# Interfase_1_Main.net
KiCad netlist of a schematic drawn in EAGLE
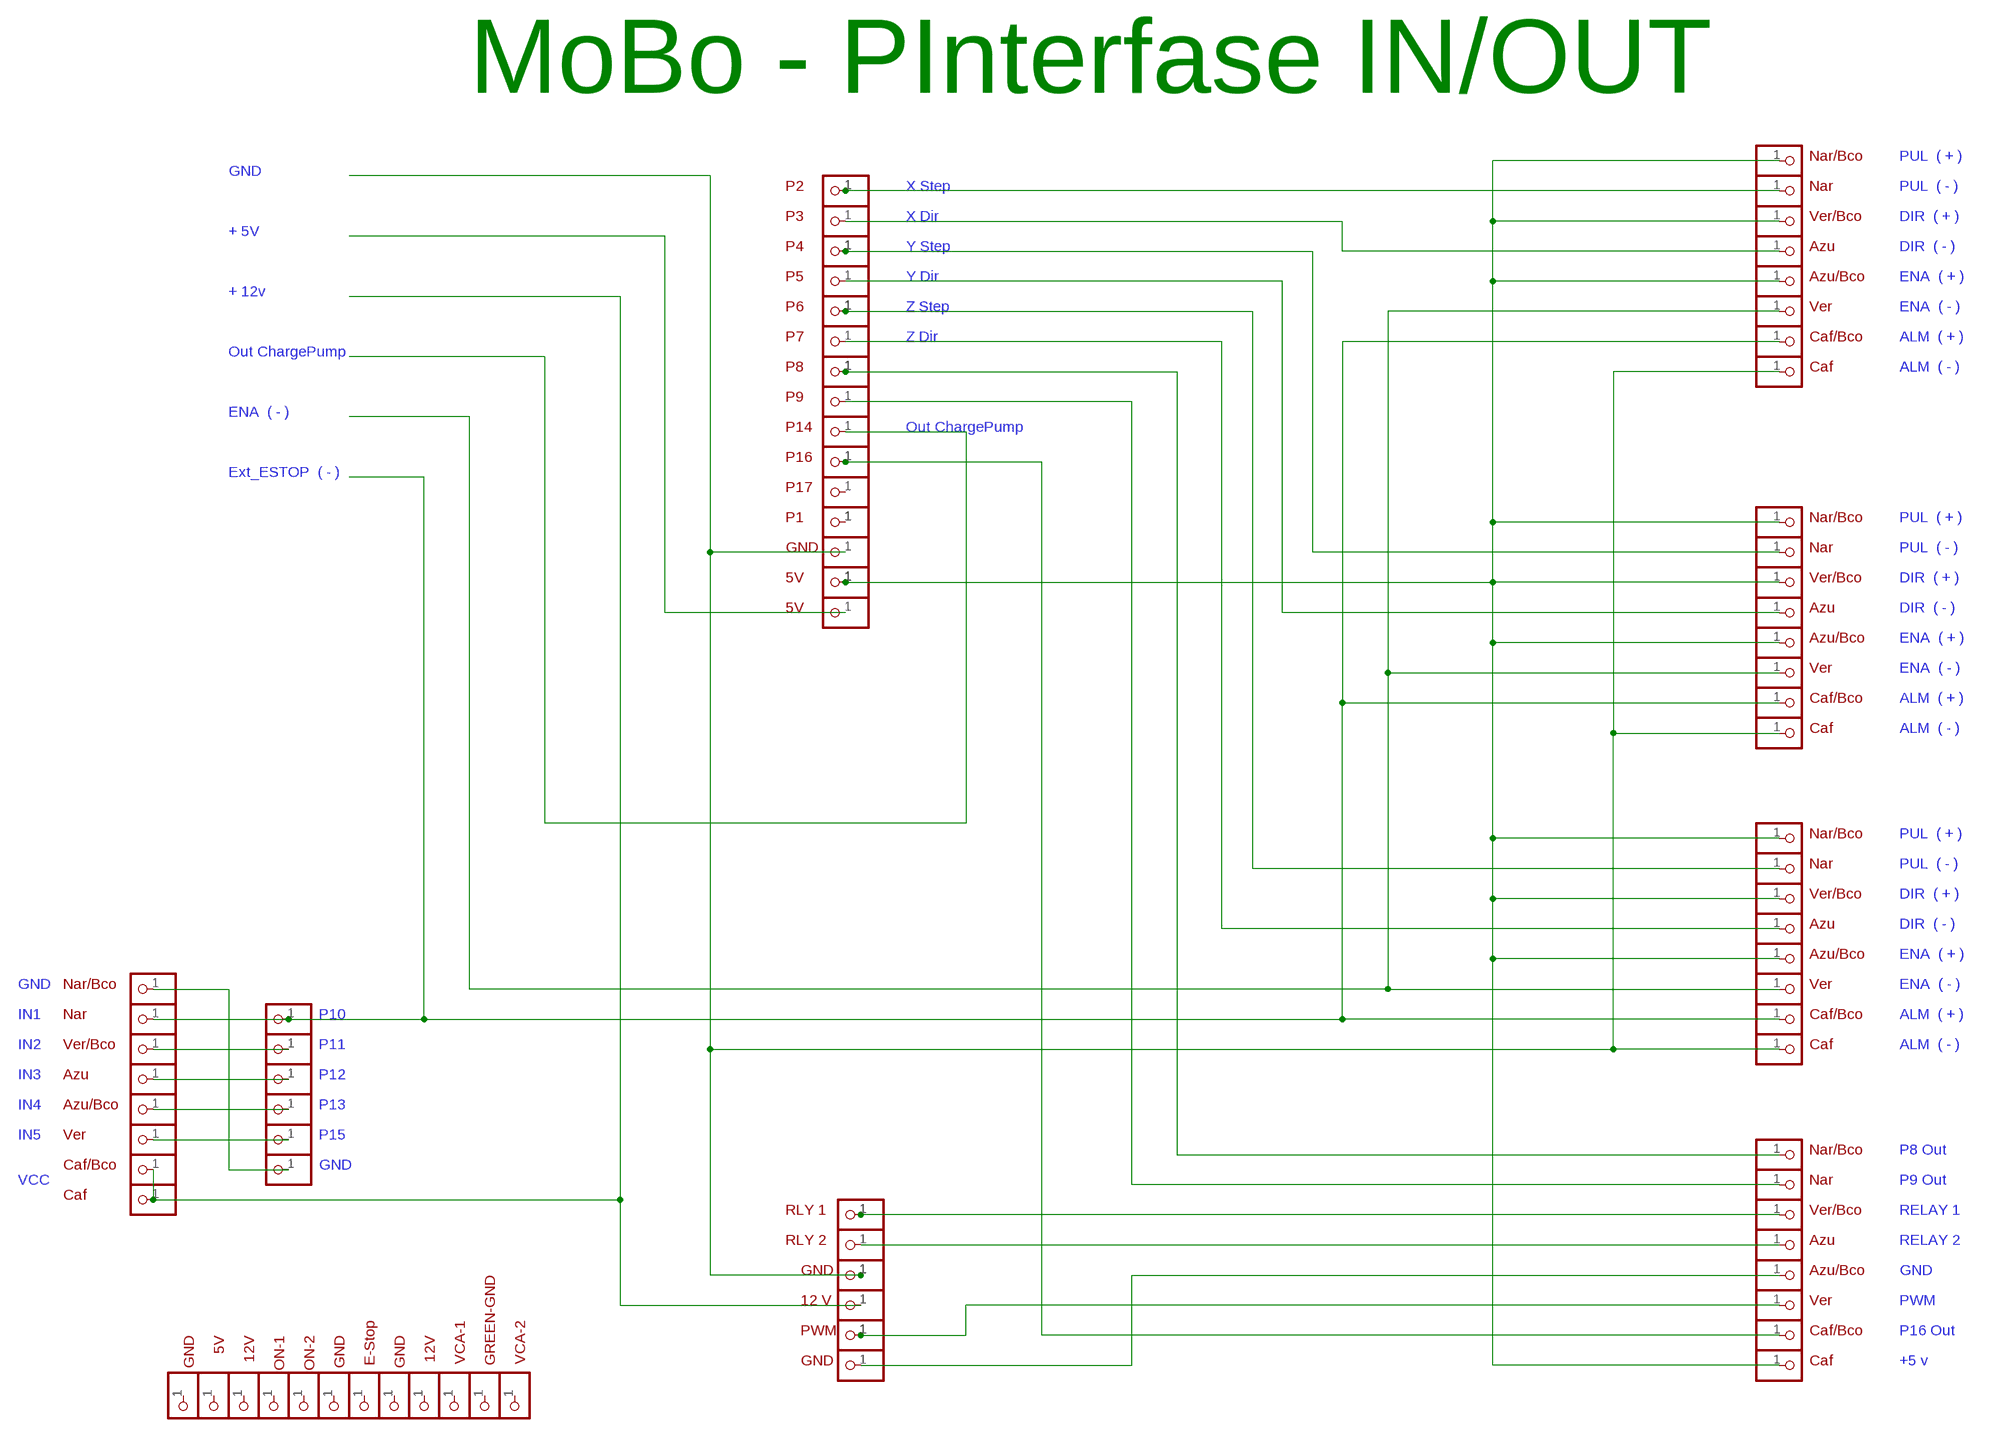
[diagram p0: schematic, sheet 1]

(export (version "E")
  (design (tool "Eeschema 10.0.6"))
  (components
    (comp (ref "JP1")
      (value "ioiooo")
      (footprint "eagle-import:1X01")
      (fields (field (name "MANUFACTURER") "Generic"))
      (libsource (lib "eagle-import") (part "PINHD-1X1"))
    )
    (comp (ref "JP2")
      (value "ioiooo")
      (footprint "eagle-import:1X01")
      (fields (field (name "MANUFACTURER") "Generic"))
      (libsource (lib "eagle-import") (part "PINHD-1X1"))
    )
    (comp (ref "JP3")
      (value "ioiooo")
      (footprint "eagle-import:1X01")
      (fields (field (name "MANUFACTURER") "Generic"))
      (libsource (lib "eagle-import") (part "PINHD-1X1"))
    )
    (comp (ref "JP4")
      (value "ioiooo")
      (footprint "eagle-import:1X01")
      (fields (field (name "MANUFACTURER") "Generic"))
      (libsource (lib "eagle-import") (part "PINHD-1X1"))
    )
    (comp (ref "JP5")
      (value "ioiooo")
      (footprint "eagle-import:1X01")
      (fields (field (name "MANUFACTURER") "Generic"))
      (libsource (lib "eagle-import") (part "PINHD-1X1"))
    )
    (comp (ref "JP6")
      (value "ioiooo")
      (footprint "eagle-import:1X01")
      (fields (field (name "MANUFACTURER") "Generic"))
      (libsource (lib "eagle-import") (part "PINHD-1X1"))
    )
    (comp (ref "JP7")
      (value "ioiooo")
      (footprint "eagle-import:1X01")
      (fields (field (name "MANUFACTURER") "Generic"))
      (libsource (lib "eagle-import") (part "PINHD-1X1"))
    )
    (comp (ref "JP8")
      (value "ioiooo")
      (footprint "eagle-import:1X01")
      (fields (field (name "MANUFACTURER") "Generic"))
      (libsource (lib "eagle-import") (part "PINHD-1X1"))
    )
    (comp (ref "JP9")
      (value "ioiooo")
      (footprint "eagle-import:1X01")
      (fields (field (name "MANUFACTURER") "Generic"))
      (libsource (lib "eagle-import") (part "PINHD-1X1"))
    )
    (comp (ref "JP10")
      (value "ioiooo")
      (footprint "eagle-import:1X01")
      (fields (field (name "MANUFACTURER") "Generic"))
      (libsource (lib "eagle-import") (part "PINHD-1X1"))
    )
    (comp (ref "JP11")
      (value "ioiooo")
      (footprint "eagle-import:1X01")
      (fields (field (name "MANUFACTURER") "Generic"))
      (libsource (lib "eagle-import") (part "PINHD-1X1"))
    )
    (comp (ref "JP12")
      (value "ioiooo")
      (footprint "eagle-import:1X01")
      (fields (field (name "MANUFACTURER") "Generic"))
      (libsource (lib "eagle-import") (part "PINHD-1X1"))
    )
    (comp (ref "JP13")
      (value "ioiooo")
      (footprint "eagle-import:1X01")
      (fields (field (name "MANUFACTURER") "Generic"))
      (libsource (lib "eagle-import") (part "PINHD-1X1"))
    )
    (comp (ref "JP14")
      (value "ioiooo")
      (footprint "eagle-import:1X01")
      (fields (field (name "MANUFACTURER") "Generic"))
      (libsource (lib "eagle-import") (part "PINHD-1X1"))
    )
    (comp (ref "JP15")
      (value "ioiooo")
      (footprint "eagle-import:1X01")
      (fields (field (name "MANUFACTURER") "Generic"))
      (libsource (lib "eagle-import") (part "PINHD-1X1"))
    )
    (comp (ref "JP16")
      (value "ioiooo")
      (footprint "eagle-import:1X01")
      (fields (field (name "MANUFACTURER") "Generic"))
      (libsource (lib "eagle-import") (part "PINHD-1X1"))
    )
    (comp (ref "JP17")
      (value "ioiooo")
      (footprint "eagle-import:1X01")
      (fields (field (name "MANUFACTURER") "Generic"))
      (libsource (lib "eagle-import") (part "PINHD-1X1"))
    )
    (comp (ref "JP18")
      (value "ioiooo")
      (footprint "eagle-import:1X01")
      (fields (field (name "MANUFACTURER") "Generic"))
      (libsource (lib "eagle-import") (part "PINHD-1X1"))
    )
    (comp (ref "JP19")
      (value "ioiooo")
      (footprint "eagle-import:1X01")
      (fields (field (name "MANUFACTURER") "Generic"))
      (libsource (lib "eagle-import") (part "PINHD-1X1"))
    )
    (comp (ref "JP20")
      (value "ioiooo")
      (footprint "eagle-import:1X01")
      (fields (field (name "MANUFACTURER") "Generic"))
      (libsource (lib "eagle-import") (part "PINHD-1X1"))
    )
    (comp (ref "JP21")
      (value "ioiooo")
      (footprint "eagle-import:1X01")
      (fields (field (name "MANUFACTURER") "Generic"))
      (libsource (lib "eagle-import") (part "PINHD-1X1"))
    )
    (comp (ref "JP22")
      (value "ioiooo")
      (footprint "eagle-import:1X01")
      (fields (field (name "MANUFACTURER") "Generic"))
      (libsource (lib "eagle-import") (part "PINHD-1X1"))
    )
    (comp (ref "JP23")
      (value "ioiooo")
      (footprint "eagle-import:1X01")
      (fields (field (name "MANUFACTURER") "Generic"))
      (libsource (lib "eagle-import") (part "PINHD-1X1"))
    )
    (comp (ref "JP24")
      (value "ioiooo")
      (footprint "eagle-import:1X01")
      (fields (field (name "MANUFACTURER") "Generic"))
      (libsource (lib "eagle-import") (part "PINHD-1X1"))
    )
    (comp (ref "JP25")
      (value "ioiooo")
      (footprint "eagle-import:1X01")
      (fields (field (name "MANUFACTURER") "Generic"))
      (libsource (lib "eagle-import") (part "PINHD-1X1"))
    )
    (comp (ref "JP26")
      (value "ioiooo")
      (footprint "eagle-import:1X01")
      (fields (field (name "MANUFACTURER") "Generic"))
      (libsource (lib "eagle-import") (part "PINHD-1X1"))
    )
    (comp (ref "JP27")
      (value "ioiooo")
      (footprint "eagle-import:1X01")
      (fields (field (name "MANUFACTURER") "Generic"))
      (libsource (lib "eagle-import") (part "PINHD-1X1"))
    )
    (comp (ref "JP28")
      (value "ioiooo")
      (footprint "eagle-import:1X01")
      (fields (field (name "MANUFACTURER") "Generic"))
      (libsource (lib "eagle-import") (part "PINHD-1X1"))
    )
    (comp (ref "JP29")
      (value "ioiooo")
      (footprint "eagle-import:1X01")
      (fields (field (name "MANUFACTURER") "Generic"))
      (libsource (lib "eagle-import") (part "PINHD-1X1"))
    )
    (comp (ref "JP30")
      (value "ioiooo")
      (footprint "eagle-import:1X01")
      (fields (field (name "MANUFACTURER") "Generic"))
      (libsource (lib "eagle-import") (part "PINHD-1X1"))
    )
    (comp (ref "JP31")
      (value "ioiooo")
      (footprint "eagle-import:1X01")
      (fields (field (name "MANUFACTURER") "Generic"))
      (libsource (lib "eagle-import") (part "PINHD-1X1"))
    )
    (comp (ref "JP32")
      (value "ioiooo")
      (footprint "eagle-import:1X01")
      (fields (field (name "MANUFACTURER") "Generic"))
      (libsource (lib "eagle-import") (part "PINHD-1X1"))
    )
    (comp (ref "JP33")
      (value "ioiooo")
      (footprint "eagle-import:1X01")
      (fields (field (name "MANUFACTURER") "Generic"))
      (libsource (lib "eagle-import") (part "PINHD-1X1"))
    )
    (comp (ref "JP34")
      (value "ioiooo")
      (footprint "eagle-import:1X01")
      (fields (field (name "MANUFACTURER") "Generic"))
      (libsource (lib "eagle-import") (part "PINHD-1X1"))
    )
    (comp (ref "JP35")
      (value "ioiooo")
      (footprint "eagle-import:1X01")
      (fields (field (name "MANUFACTURER") "Generic"))
      (libsource (lib "eagle-import") (part "PINHD-1X1"))
    )
    (comp (ref "JP36")
      (value "ioiooo")
      (footprint "eagle-import:1X01")
      (fields (field (name "MANUFACTURER") "Generic"))
      (libsource (lib "eagle-import") (part "PINHD-1X1"))
    )
    (comp (ref "JP37")
      (value "ioiooo")
      (footprint "eagle-import:1X01")
      (fields (field (name "MANUFACTURER") "Generic"))
      (libsource (lib "eagle-import") (part "PINHD-1X1"))
    )
    (comp (ref "JP38")
      (value "ioiooo")
      (footprint "eagle-import:1X01")
      (fields (field (name "MANUFACTURER") "Generic"))
      (libsource (lib "eagle-import") (part "PINHD-1X1"))
    )
    (comp (ref "JP39")
      (value "ioiooo")
      (footprint "eagle-import:1X01")
      (fields (field (name "MANUFACTURER") "Generic"))
      (libsource (lib "eagle-import") (part "PINHD-1X1"))
    )
    (comp (ref "JP40")
      (value "ioiooo")
      (footprint "eagle-import:1X01")
      (fields (field (name "MANUFACTURER") "Generic"))
      (libsource (lib "eagle-import") (part "PINHD-1X1"))
    )
    (comp (ref "JP41")
      (value "ioiooo")
      (footprint "eagle-import:1X01")
      (fields (field (name "MANUFACTURER") "Generic"))
      (libsource (lib "eagle-import") (part "PINHD-1X1"))
    )
    (comp (ref "JP42")
      (value "ioiooo")
      (footprint "eagle-import:1X01")
      (fields (field (name "MANUFACTURER") "Generic"))
      (libsource (lib "eagle-import") (part "PINHD-1X1"))
    )
    (comp (ref "JP43")
      (value "ioiooo")
      (footprint "eagle-import:1X01")
      (fields (field (name "MANUFACTURER") "Generic"))
      (libsource (lib "eagle-import") (part "PINHD-1X1"))
    )
    (comp (ref "JP44")
      (value "ioiooo")
      (footprint "eagle-import:1X01")
      (fields (field (name "MANUFACTURER") "Generic"))
      (libsource (lib "eagle-import") (part "PINHD-1X1"))
    )
    (comp (ref "JP45")
      (value "ioiooo")
      (footprint "eagle-import:1X01")
      (fields (field (name "MANUFACTURER") "Generic"))
      (libsource (lib "eagle-import") (part "PINHD-1X1"))
    )
    (comp (ref "JP46")
      (value "ioiooo")
      (footprint "eagle-import:1X01")
      (fields (field (name "MANUFACTURER") "Generic"))
      (libsource (lib "eagle-import") (part "PINHD-1X1"))
    )
    (comp (ref "JP47")
      (value "ioiooo")
      (footprint "eagle-import:1X01")
      (fields (field (name "MANUFACTURER") "Generic"))
      (libsource (lib "eagle-import") (part "PINHD-1X1"))
    )
    (comp (ref "JP48")
      (value "ioiooo")
      (footprint "eagle-import:1X01")
      (fields (field (name "MANUFACTURER") "Generic"))
      (libsource (lib "eagle-import") (part "PINHD-1X1"))
    )
    (comp (ref "JP49")
      (value "ioiooo")
      (footprint "eagle-import:1X01")
      (fields (field (name "MANUFACTURER") "Generic"))
      (libsource (lib "eagle-import") (part "PINHD-1X1"))
    )
    (comp (ref "JP50")
      (value "ioiooo")
      (footprint "eagle-import:1X01")
      (fields (field (name "MANUFACTURER") "Generic"))
      (libsource (lib "eagle-import") (part "PINHD-1X1"))
    )
    (comp (ref "JP51")
      (value "ioiooo")
      (footprint "eagle-import:1X01")
      (fields (field (name "MANUFACTURER") "Generic"))
      (libsource (lib "eagle-import") (part "PINHD-1X1"))
    )
    (comp (ref "JP52")
      (value "ioiooo")
      (footprint "eagle-import:1X01")
      (fields (field (name "MANUFACTURER") "Generic"))
      (libsource (lib "eagle-import") (part "PINHD-1X1"))
    )
    (comp (ref "JP53")
      (value "ioiooo")
      (footprint "eagle-import:1X01")
      (fields (field (name "MANUFACTURER") "Generic"))
      (libsource (lib "eagle-import") (part "PINHD-1X1"))
    )
    (comp (ref "JP54")
      (value "ioiooo")
      (footprint "eagle-import:1X01")
      (fields (field (name "MANUFACTURER") "Generic"))
      (libsource (lib "eagle-import") (part "PINHD-1X1"))
    )
    (comp (ref "JP55")
      (value "ioiooo")
      (footprint "eagle-import:1X01")
      (fields (field (name "MANUFACTURER") "Generic"))
      (libsource (lib "eagle-import") (part "PINHD-1X1"))
    )
    (comp (ref "JP56")
      (value "ioiooo")
      (footprint "eagle-import:1X01")
      (fields (field (name "MANUFACTURER") "Generic"))
      (libsource (lib "eagle-import") (part "PINHD-1X1"))
    )
    (comp (ref "JP57")
      (value "ioiooo")
      (footprint "eagle-import:1X01")
      (fields (field (name "MANUFACTURER") "Generic"))
      (libsource (lib "eagle-import") (part "PINHD-1X1"))
    )
    (comp (ref "JP58")
      (value "ioiooo")
      (footprint "eagle-import:1X01")
      (fields (field (name "MANUFACTURER") "Generic"))
      (libsource (lib "eagle-import") (part "PINHD-1X1"))
    )
    (comp (ref "JP59")
      (value "ioiooo")
      (footprint "eagle-import:1X01")
      (fields (field (name "MANUFACTURER") "Generic"))
      (libsource (lib "eagle-import") (part "PINHD-1X1"))
    )
    (comp (ref "JP60")
      (value "ioiooo")
      (footprint "eagle-import:1X01")
      (fields (field (name "MANUFACTURER") "Generic"))
      (libsource (lib "eagle-import") (part "PINHD-1X1"))
    )
    (comp (ref "JP61")
      (value "ioiooo")
      (footprint "eagle-import:1X01")
      (fields (field (name "MANUFACTURER") "Generic"))
      (libsource (lib "eagle-import") (part "PINHD-1X1"))
    )
    (comp (ref "JP62")
      (value "ioiooo")
      (footprint "eagle-import:1X01")
      (fields (field (name "MANUFACTURER") "Generic"))
      (libsource (lib "eagle-import") (part "PINHD-1X1"))
    )
    (comp (ref "JP63")
      (value "ioiooo")
      (footprint "eagle-import:1X01")
      (fields (field (name "MANUFACTURER") "Generic"))
      (libsource (lib "eagle-import") (part "PINHD-1X1"))
    )
    (comp (ref "JP64")
      (value "ioiooo")
      (footprint "eagle-import:1X01")
      (fields (field (name "MANUFACTURER") "Generic"))
      (libsource (lib "eagle-import") (part "PINHD-1X1"))
    )
    (comp (ref "JP65")
      (value "ioiooo")
      (footprint "eagle-import:1X01")
      (fields (field (name "MANUFACTURER") "Generic"))
      (libsource (lib "eagle-import") (part "PINHD-1X1"))
    )
    (comp (ref "JP66")
      (value "ioiooo")
      (footprint "eagle-import:1X01")
      (fields (field (name "MANUFACTURER") "Generic"))
      (libsource (lib "eagle-import") (part "PINHD-1X1"))
    )
    (comp (ref "JP67")
      (value "ioiooo")
      (footprint "eagle-import:1X01")
      (fields (field (name "MANUFACTURER") "Generic"))
      (libsource (lib "eagle-import") (part "PINHD-1X1"))
    )
    (comp (ref "JP68")
      (value "ioiooo")
      (footprint "eagle-import:1X01")
      (fields (field (name "MANUFACTURER") "Generic"))
      (libsource (lib "eagle-import") (part "PINHD-1X1"))
    )
    (comp (ref "JP69")
      (value "ioiooo")
      (footprint "eagle-import:1X01")
      (fields (field (name "MANUFACTURER") "Generic"))
      (libsource (lib "eagle-import") (part "PINHD-1X1"))
    )
    (comp (ref "JP70")
      (value "ioiooo")
      (footprint "eagle-import:1X01")
      (fields (field (name "MANUFACTURER") "Generic"))
      (libsource (lib "eagle-import") (part "PINHD-1X1"))
    )
    (comp (ref "JP71")
      (value "ioiooo")
      (footprint "eagle-import:1X01")
      (fields (field (name "MANUFACTURER") "Generic"))
      (libsource (lib "eagle-import") (part "PINHD-1X1"))
    )
    (comp (ref "JP72")
      (value "ioiooo")
      (footprint "eagle-import:1X01")
      (fields (field (name "MANUFACTURER") "Generic"))
      (libsource (lib "eagle-import") (part "PINHD-1X1"))
    )
    (comp (ref "JP73")
      (value "ioiooo")
      (footprint "eagle-import:1X01")
      (fields (field (name "MANUFACTURER") "Generic"))
      (libsource (lib "eagle-import") (part "PINHD-1X1"))
    )
    (comp (ref "JP74")
      (value "ioiooo")
      (footprint "eagle-import:1X01")
      (fields (field (name "MANUFACTURER") "Generic"))
      (libsource (lib "eagle-import") (part "PINHD-1X1"))
    )
    (comp (ref "JP75")
      (value "ioiooo")
      (footprint "eagle-import:1X01")
      (fields (field (name "MANUFACTURER") "Generic"))
      (libsource (lib "eagle-import") (part "PINHD-1X1"))
    )
    (comp (ref "JP76")
      (value "ioiooo")
      (footprint "eagle-import:1X01")
      (fields (field (name "MANUFACTURER") "Generic"))
      (libsource (lib "eagle-import") (part "PINHD-1X1"))
    )
    (comp (ref "JP77")
      (value "ioiooo")
      (footprint "eagle-import:1X01")
      (fields (field (name "MANUFACTURER") "Generic"))
      (libsource (lib "eagle-import") (part "PINHD-1X1"))
    )
    (comp (ref "JP78")
      (value "ioiooo")
      (footprint "eagle-import:1X01")
      (fields (field (name "MANUFACTURER") "Generic"))
      (libsource (lib "eagle-import") (part "PINHD-1X1"))
    )
    (comp (ref "JP79")
      (value "ioiooo")
      (footprint "eagle-import:1X01")
      (fields (field (name "MANUFACTURER") "Generic"))
      (libsource (lib "eagle-import") (part "PINHD-1X1"))
    )
    (comp (ref "JP80")
      (value "ioiooo")
      (footprint "eagle-import:1X01")
      (fields (field (name "MANUFACTURER") "Generic"))
      (libsource (lib "eagle-import") (part "PINHD-1X1"))
    )
    (comp (ref "JP81")
      (value "ioiooo")
      (footprint "eagle-import:1X01")
      (fields (field (name "MANUFACTURER") "Generic"))
      (libsource (lib "eagle-import") (part "PINHD-1X1"))
    )
    (comp (ref "JP82")
      (value "ioiooo")
      (footprint "eagle-import:1X01")
      (fields (field (name "MANUFACTURER") "Generic"))
      (libsource (lib "eagle-import") (part "PINHD-1X1"))
    )
    (comp (ref "JP83")
      (value "ioiooo")
      (footprint "eagle-import:1X01")
      (fields (field (name "MANUFACTURER") "Generic"))
      (libsource (lib "eagle-import") (part "PINHD-1X1"))
    )
    (comp (ref "JP84")
      (value "ioiooo")
      (footprint "eagle-import:1X01")
      (fields (field (name "MANUFACTURER") "Generic"))
      (libsource (lib "eagle-import") (part "PINHD-1X1"))
    )
    (comp (ref "JP85")
      (value "ioiooo")
      (footprint "eagle-import:1X01")
      (fields (field (name "MANUFACTURER") "Generic"))
      (libsource (lib "eagle-import") (part "PINHD-1X1"))
    )
    (comp (ref "JP86")
      (value "ioiooo")
      (footprint "eagle-import:1X01")
      (fields (field (name "MANUFACTURER") "Generic"))
      (libsource (lib "eagle-import") (part "PINHD-1X1"))
    )
    (comp (ref "JP87")
      (value "ioiooo")
      (footprint "eagle-import:1X01")
      (fields (field (name "MANUFACTURER") "Generic"))
      (libsource (lib "eagle-import") (part "PINHD-1X1"))
    )
    (comp (ref "JP88")
      (value "ioiooo")
      (footprint "eagle-import:1X01")
      (fields (field (name "MANUFACTURER") "Generic"))
      (libsource (lib "eagle-import") (part "PINHD-1X1"))
    )
    (comp (ref "JP89")
      (value "ioiooo")
      (footprint "eagle-import:1X01")
      (fields (field (name "MANUFACTURER") "Generic"))
      (libsource (lib "eagle-import") (part "PINHD-1X1"))
    )
  )
  (nets
    (net (code "1") (name "Net-(JP1-Pad1)") (class "Default")
      (node (ref "JP1") (pin "1") (pinfunction "1_1") (pintype "passive"))
      (node (ref "JP15") (pin "1") (pinfunction "1_1") (pintype "passive"))
      (node (ref "JP17") (pin "1") (pinfunction "1_1") (pintype "passive"))
      (node (ref "JP29") (pin "1") (pinfunction "1_1") (pintype "passive"))
      (node (ref "JP31") (pin "1") (pinfunction "1_1") (pintype "passive"))
      (node (ref "JP32") (pin "1") (pinfunction "1_1") (pintype "passive"))
      (node (ref "JP35") (pin "1") (pinfunction "1_1") (pintype "passive"))
      (node (ref "JP37") (pin "1") (pinfunction "1_1") (pintype "passive"))
      (node (ref "JP41") (pin "1") (pinfunction "1_1") (pintype "passive"))
      (node (ref "JP43") (pin "1") (pinfunction "1_1") (pintype "passive"))
      (node (ref "JP45") (pin "1") (pinfunction "1_1") (pintype "passive"))
      (node (ref "JP54") (pin "1") (pinfunction "1_1") (pintype "passive"))
    )
    (net (code "2") (name "Net-(JP2-Pad1)") (class "Default")
      (node (ref "JP2") (pin "1") (pinfunction "1_1") (pintype "passive"))
      (node (ref "JP3") (pin "1") (pinfunction "1_1") (pintype "passive"))
      (node (ref "JP4") (pin "1") (pinfunction "1_1") (pintype "passive"))
    )
    (net (code "3") (name "Net-(JP10-Pad1)") (class "Default")
      (node (ref "JP10") (pin "1") (pinfunction "1_1") (pintype "passive"))
      (node (ref "JP42") (pin "1") (pinfunction "1_1") (pintype "passive"))
      (node (ref "JP9") (pin "1") (pinfunction "1_1") (pintype "passive"))
    )
    (net (code "4") (name "Net-(JP11-Pad1)") (class "Default")
      (node (ref "JP11") (pin "1") (pinfunction "1_1") (pintype "passive"))
      (node (ref "JP44") (pin "1") (pinfunction "1_1") (pintype "passive"))
    )
    (net (code "5") (name "Net-(JP12-Pad1)") (class "Default")
      (node (ref "JP12") (pin "1") (pinfunction "1_1") (pintype "passive"))
      (node (ref "JP13") (pin "1") (pinfunction "1_1") (pintype "passive"))
      (node (ref "JP27") (pin "1") (pinfunction "1_1") (pintype "passive"))
    )
    (net (code "6") (name "Net-(JP14-Pad1)") (class "Default")
      (node (ref "JP14") (pin "1") (pinfunction "1_1") (pintype "passive"))
      (node (ref "JP28") (pin "1") (pinfunction "1_1") (pintype "passive"))
    )
    (net (code "7") (name "Net-(JP16-Pad1)") (class "Default")
      (node (ref "JP16") (pin "1") (pinfunction "1_1") (pintype "passive"))
      (node (ref "JP5") (pin "1") (pinfunction "1_1") (pintype "passive"))
    )
    (net (code "8") (name "Net-(JP18-Pad1)") (class "Default")
      (node (ref "JP18") (pin "1") (pinfunction "1_1") (pintype "passive"))
      (node (ref "JP38") (pin "1") (pinfunction "1_1") (pintype "passive"))
      (node (ref "JP46") (pin "1") (pinfunction "1_1") (pintype "passive"))
    )
    (net (code "9") (name "Net-(JP19-Pad1)") (class "Default")
      (node (ref "JP19") (pin "1") (pinfunction "1_1") (pintype "passive"))
      (node (ref "JP39") (pin "1") (pinfunction "1_1") (pintype "passive"))
      (node (ref "JP47") (pin "1") (pinfunction "1_1") (pintype "passive"))
      (node (ref "JP64") (pin "1") (pinfunction "1_1") (pintype "passive"))
      (node (ref "JP70") (pin "1") (pinfunction "1_1") (pintype "passive"))
    )
    (net (code "10") (name "Net-(JP20-Pad1)") (class "Default")
      (node (ref "JP20") (pin "1") (pinfunction "1_1") (pintype "passive"))
      (node (ref "JP30") (pin "1") (pinfunction "1_1") (pintype "passive"))
      (node (ref "JP40") (pin "1") (pinfunction "1_1") (pintype "passive"))
      (node (ref "JP48") (pin "1") (pinfunction "1_1") (pintype "passive"))
      (node (ref "JP58") (pin "1") (pinfunction "1_1") (pintype "passive"))
      (node (ref "JP59") (pin "1") (pinfunction "1_1") (pintype "passive"))
    )
    (net (code "11") (name "Net-(JP22-Pad1)") (class "Default")
      (node (ref "JP22") (pin "1") (pinfunction "1_1") (pintype "passive"))
      (node (ref "JP23") (pin "1") (pinfunction "1_1") (pintype "passive"))
      (node (ref "JP53") (pin "1") (pinfunction "1_1") (pintype "passive"))
    )
    (net (code "12") (name "Net-(JP25-Pad1)") (class "Default")
      (node (ref "JP25") (pin "1") (pinfunction "1_1") (pintype "passive"))
      (node (ref "JP26") (pin "1") (pinfunction "1_1") (pintype "passive"))
    )
    (net (code "13") (name "Net-(JP34-Pad1)") (class "Default")
      (node (ref "JP34") (pin "1") (pinfunction "1_1") (pintype "passive"))
      (node (ref "JP6") (pin "1") (pinfunction "1_1") (pintype "passive"))
      (node (ref "JP7") (pin "1") (pinfunction "1_1") (pintype "passive"))
    )
    (net (code "14") (name "Net-(JP36-Pad1)") (class "Default")
      (node (ref "JP36") (pin "1") (pinfunction "1_1") (pintype "passive"))
      (node (ref "JP8") (pin "1") (pinfunction "1_1") (pintype "passive"))
    )
    (net (code "15") (name "Net-(JP49-Pad1)") (class "Default")
      (node (ref "JP49") (pin "1") (pinfunction "1_1") (pintype "passive"))
      (node (ref "JP55") (pin "1") (pinfunction "1_1") (pintype "passive"))
      (node (ref "JP56") (pin "1") (pinfunction "1_1") (pintype "passive"))
    )
    (net (code "16") (name "Net-(JP50-Pad1)") (class "Default")
      (node (ref "JP50") (pin "1") (pinfunction "1_1") (pintype "passive"))
      (node (ref "JP57") (pin "1") (pinfunction "1_1") (pintype "passive"))
    )
    (net (code "17") (name "Net-(JP51-Pad1)") (class "Default")
      (node (ref "JP51") (pin "1") (pinfunction "1_1") (pintype "passive"))
      (node (ref "JP63") (pin "1") (pinfunction "1_1") (pintype "passive"))
    )
    (net (code "18") (name "Net-(JP52-Pad1)") (class "Default")
      (node (ref "JP52") (pin "1") (pinfunction "1_1") (pintype "passive"))
      (node (ref "JP61") (pin "1") (pinfunction "1_1") (pintype "passive"))
      (node (ref "JP62") (pin "1") (pinfunction "1_1") (pintype "passive"))
    )
    (net (code "19") (name "Net-(JP60-Pad1)") (class "Default")
      (node (ref "JP60") (pin "1") (pinfunction "1_1") (pintype "passive"))
      (node (ref "JP75") (pin "1") (pinfunction "1_1") (pintype "passive"))
      (node (ref "JP77") (pin "1") (pinfunction "1_1") (pintype "passive"))
    )
    (net (code "20") (name "Net-(JP65-Pad1)") (class "Default")
      (node (ref "JP65") (pin "1") (pinfunction "1_1") (pintype "passive"))
      (node (ref "JP71") (pin "1") (pinfunction "1_1") (pintype "passive"))
    )
    (net (code "21") (name "Net-(JP66-Pad1)") (class "Default")
      (node (ref "JP66") (pin "1") (pinfunction "1_1") (pintype "passive"))
      (node (ref "JP72") (pin "1") (pinfunction "1_1") (pintype "passive"))
    )
    (net (code "22") (name "Net-(JP67-Pad1)") (class "Default")
      (node (ref "JP67") (pin "1") (pinfunction "1_1") (pintype "passive"))
      (node (ref "JP73") (pin "1") (pinfunction "1_1") (pintype "passive"))
    )
    (net (code "23") (name "Net-(JP68-Pad1)") (class "Default")
      (node (ref "JP68") (pin "1") (pinfunction "1_1") (pintype "passive"))
      (node (ref "JP74") (pin "1") (pinfunction "1_1") (pintype "passive"))
    )
    (net (code "24") (name "Net-(JP69-Pad1)") (class "Default")
      (node (ref "JP69") (pin "1") (pinfunction "1_1") (pintype "passive"))
      (node (ref "JP76") (pin "1") (pinfunction "1_1") (pintype "passive"))
    )
    (net (code "25") (name "unconnected-(JP21-Pad1)") (class "Default")
      (node (ref "JP21") (pin "1") (pinfunction "1_1") (pintype "passive"))
    )
    (net (code "26") (name "unconnected-(JP24-Pad1)") (class "Default")
      (node (ref "JP24") (pin "1") (pinfunction "1_1") (pintype "passive"))
    )
    (net (code "27") (name "unconnected-(JP33-Pad1)") (class "Default")
      (node (ref "JP33") (pin "1") (pinfunction "1_1") (pintype "passive"))
    )
    (net (code "28") (name "unconnected-(JP78-Pad1)") (class "Default")
      (node (ref "JP78") (pin "1") (pinfunction "1_1") (pintype "passive"))
    )
    (net (code "29") (name "unconnected-(JP79-Pad1)") (class "Default")
      (node (ref "JP79") (pin "1") (pinfunction "1_1") (pintype "passive"))
    )
    (net (code "30") (name "unconnected-(JP80-Pad1)") (class "Default")
      (node (ref "JP80") (pin "1") (pinfunction "1_1") (pintype "passive"))
    )
    (net (code "31") (name "unconnected-(JP81-Pad1)") (class "Default")
      (node (ref "JP81") (pin "1") (pinfunction "1_1") (pintype "passive"))
    )
    (net (code "32") (name "unconnected-(JP82-Pad1)") (class "Default")
      (node (ref "JP82") (pin "1") (pinfunction "1_1") (pintype "passive"))
    )
    (net (code "33") (name "unconnected-(JP83-Pad1)") (class "Default")
      (node (ref "JP83") (pin "1") (pinfunction "1_1") (pintype "passive"))
    )
    (net (code "34") (name "unconnected-(JP84-Pad1)") (class "Default")
      (node (ref "JP84") (pin "1") (pinfunction "1_1") (pintype "passive"))
    )
    (net (code "35") (name "unconnected-(JP85-Pad1)") (class "Default")
      (node (ref "JP85") (pin "1") (pinfunction "1_1") (pintype "passive"))
    )
    (net (code "36") (name "unconnected-(JP86-Pad1)") (class "Default")
      (node (ref "JP86") (pin "1") (pinfunction "1_1") (pintype "passive"))
    )
    (net (code "37") (name "unconnected-(JP87-Pad1)") (class "Default")
      (node (ref "JP87") (pin "1") (pinfunction "1_1") (pintype "passive"))
    )
    (net (code "38") (name "unconnected-(JP88-Pad1)") (class "Default")
      (node (ref "JP88") (pin "1") (pinfunction "1_1") (pintype "passive"))
    )
    (net (code "39") (name "unconnected-(JP89-Pad1)") (class "Default")
      (node (ref "JP89") (pin "1") (pinfunction "1_1") (pintype "passive"))
    )
  )
)
